# LIN-INTERFACES.net
KiCad netlist of a schematic drawn in Altium Designer
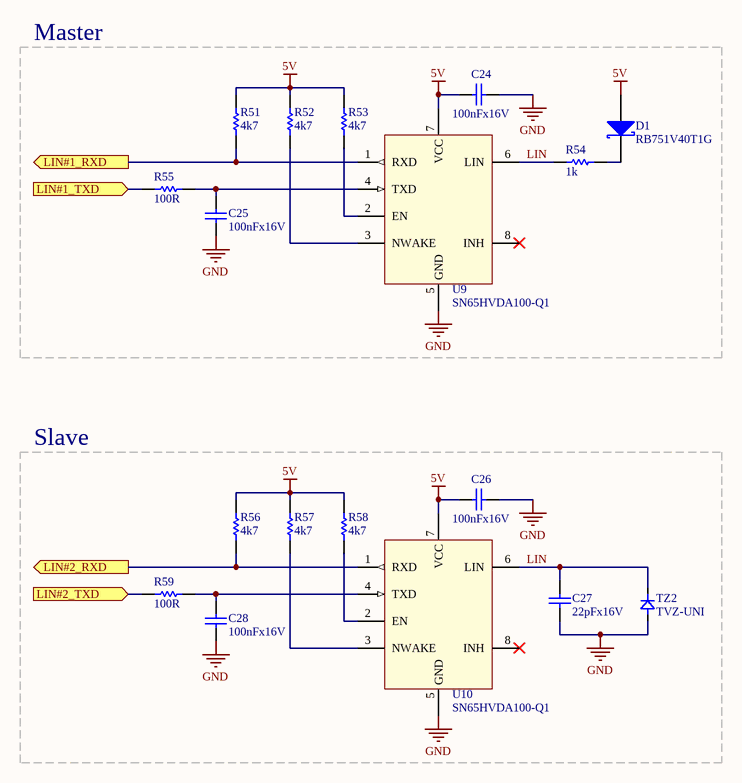
[diagram p0: LIN-INTERFACES.SchDoc]

(export (version "E")
  (design (tool "Eeschema 10.0.6"))
  (components
    (comp (ref "C24")
      (value "100nFx16V")
      (footprint "DISC-0603")
      (description "Capacitor")
      (libsource (lib "IntLib") (part "Cap"))
    )
    (comp (ref "C25")
      (value "100nFx16V")
      (footprint "DISC-0603")
      (description "Capacitor")
      (libsource (lib "IntLib") (part "Cap"))
    )
    (comp (ref "C26")
      (value "100nFx16V")
      (footprint "DISC-0603")
      (description "Capacitor")
      (libsource (lib "IntLib") (part "Cap"))
    )
    (comp (ref "C27") (value "22pFx16V") (footprint "DISC-0603") (libsource (lib "IntLib") (part "Cap")))
    (comp (ref "C28")
      (value "100nFx16V")
      (footprint "DISC-0603")
      (description "Capacitor")
      (libsource (lib "IntLib") (part "Cap"))
    )
    (comp (ref "D1")
      (value "RB751V40T1G")
      (footprint "DISC-SOD-323")
      (description "Schottky Diode")
      (fields (field (name "PUBLISHER") "Altium Limited"))
      (libsource (lib "IntLib") (part "D Schottky"))
    )
    (comp (ref "R51")
      (value "4k7")
      (footprint "DISC-0603")
      (description "Resistor")
      (libsource (lib "IntLib") (part "Res"))
    )
    (comp (ref "R52")
      (value "4k7")
      (footprint "DISC-0603")
      (description "Resistor")
      (libsource (lib "IntLib") (part "Res"))
    )
    (comp (ref "R53")
      (value "4k7")
      (footprint "DISC-0603")
      (description "Resistor")
      (libsource (lib "IntLib") (part "Res"))
    )
    (comp (ref "R54")
      (value "1k")
      (footprint "DISC-0603")
      (description "Resistor")
      (libsource (lib "IntLib") (part "Res"))
    )
    (comp (ref "R55")
      (value "100R")
      (footprint "DISC-0603")
      (description "Resistor")
      (libsource (lib "IntLib") (part "Res"))
    )
    (comp (ref "R56")
      (value "4k7")
      (footprint "DISC-0603")
      (description "Resistor")
      (libsource (lib "IntLib") (part "Res"))
    )
    (comp (ref "R57")
      (value "4k7")
      (footprint "DISC-0603")
      (description "Resistor")
      (libsource (lib "IntLib") (part "Res"))
    )
    (comp (ref "R58")
      (value "4k7")
      (footprint "DISC-0603")
      (description "Resistor")
      (libsource (lib "IntLib") (part "Res"))
    )
    (comp (ref "R59")
      (value "100R")
      (footprint "DISC-0603")
      (description "Resistor")
      (libsource (lib "IntLib") (part "Res"))
    )
    (comp (ref "TZ2")
      (value "TVZ-UNI")
      (footprint "DISC-SOD-323")
      (description "TVZ-Unidirectional")
      (libsource (lib "IntLib") (part "TVZ-Unidirectional"))
    )
    (comp (ref "U9")
      (value "SN65HVDA100-Q1")
      (footprint "CI-SOIC-8")
      (description "LIN Transceiver")
      (libsource (lib "IntLib") (part "SN65HVDA100-Q1"))
    )
    (comp (ref "U10")
      (value "SN65HVDA100-Q1")
      (footprint "CI-SOIC-8")
      (description "LIN Transceiver")
      (libsource (lib "IntLib") (part "SN65HVDA100-Q1"))
    )
  )
  (nets
    (net (code "1") (name "/LIN") (class "Default")
      (node (ref "C27") (pin "2") (pinfunction "2_2") (pintype "passive"))
      (node (ref "R54") (pin "2") (pinfunction "2_2") (pintype "passive"))
      (node (ref "TZ2") (pin "2") (pinfunction "C_2") (pintype "passive"))
      (node (ref "U10") (pin "6") (pinfunction "LIN_6") (pintype "passive"))
      (node (ref "U9") (pin "6") (pinfunction "LIN_6") (pintype "passive"))
    )
    (net (code "2") (name "/LIN#1_RXD") (class "Default")
      (node (ref "R51") (pin "1") (pinfunction "1_1") (pintype "passive"))
      (node (ref "U9") (pin "1") (pinfunction "RXD_1") (pintype "output"))
    )
    (net (code "3") (name "/LIN#1_TXD") (class "Default")
      (node (ref "R55") (pin "2") (pinfunction "2_2") (pintype "passive"))
    )
    (net (code "4") (name "/LIN#2_RXD") (class "Default")
      (node (ref "R56") (pin "1") (pinfunction "1_1") (pintype "passive"))
      (node (ref "U10") (pin "1") (pinfunction "RXD_1") (pintype "output"))
    )
    (net (code "5") (name "/LIN#2_TXD") (class "Default")
      (node (ref "R59") (pin "2") (pinfunction "2_2") (pintype "passive"))
    )
    (net (code "6") (name "5V") (class "Default")
      (node (ref "C24") (pin "2") (pinfunction "2_2") (pintype "passive"))
      (node (ref "C26") (pin "2") (pinfunction "2_2") (pintype "passive"))
      (node (ref "D1") (pin "1") (pinfunction "A_1") (pintype "passive"))
      (node (ref "R51") (pin "2") (pinfunction "2_2") (pintype "passive"))
      (node (ref "R52") (pin "2") (pinfunction "2_2") (pintype "passive"))
      (node (ref "R53") (pin "2") (pinfunction "2_2") (pintype "passive"))
      (node (ref "R56") (pin "2") (pinfunction "2_2") (pintype "passive"))
      (node (ref "R57") (pin "2") (pinfunction "2_2") (pintype "passive"))
      (node (ref "R58") (pin "2") (pinfunction "2_2") (pintype "passive"))
      (node (ref "U10") (pin "7") (pinfunction "VCC_7") (pintype "power_in"))
      (node (ref "U9") (pin "7") (pinfunction "VCC_7") (pintype "power_in"))
    )
    (net (code "7") (name "GND") (class "Default")
      (node (ref "C24") (pin "1") (pinfunction "1_1") (pintype "passive"))
      (node (ref "C25") (pin "1") (pinfunction "1_1") (pintype "passive"))
      (node (ref "C26") (pin "1") (pinfunction "1_1") (pintype "passive"))
      (node (ref "C27") (pin "1") (pinfunction "1_1") (pintype "passive"))
      (node (ref "C28") (pin "1") (pinfunction "1_1") (pintype "passive"))
      (node (ref "TZ2") (pin "1") (pinfunction "A_1") (pintype "passive"))
      (node (ref "U10") (pin "5") (pinfunction "GND_5") (pintype "power_in"))
      (node (ref "U9") (pin "5") (pinfunction "GND_5") (pintype "power_in"))
    )
    (net (code "8") (name "Net-(D1-K)") (class "Default")
      (node (ref "D1") (pin "2") (pinfunction "K_2") (pintype "passive"))
      (node (ref "R54") (pin "1") (pinfunction "1_1") (pintype "passive"))
    )
    (net (code "9") (name "Net-(U9-EN)") (class "Default")
      (node (ref "R53") (pin "1") (pinfunction "1_1") (pintype "passive"))
      (node (ref "U9") (pin "2") (pinfunction "EN_2") (pintype "passive"))
    )
    (net (code "10") (name "Net-(U9-NWAKE)") (class "Default")
      (node (ref "R52") (pin "1") (pinfunction "1_1") (pintype "passive"))
      (node (ref "U9") (pin "3") (pinfunction "NWAKE_3") (pintype "passive"))
    )
    (net (code "11") (name "Net-(U9-TXD)") (class "Default")
      (node (ref "C25") (pin "2") (pinfunction "2_2") (pintype "passive"))
      (node (ref "R55") (pin "1") (pinfunction "1_1") (pintype "passive"))
      (node (ref "U9") (pin "4") (pinfunction "TXD_4") (pintype "input"))
    )
    (net (code "12") (name "Net-(U10-EN)") (class "Default")
      (node (ref "R58") (pin "1") (pinfunction "1_1") (pintype "passive"))
      (node (ref "U10") (pin "2") (pinfunction "EN_2") (pintype "passive"))
    )
    (net (code "13") (name "Net-(U10-NWAKE)") (class "Default")
      (node (ref "R57") (pin "1") (pinfunction "1_1") (pintype "passive"))
      (node (ref "U10") (pin "3") (pinfunction "NWAKE_3") (pintype "passive"))
    )
    (net (code "14") (name "Net-(U10-TXD)") (class "Default")
      (node (ref "C28") (pin "2") (pinfunction "2_2") (pintype "passive"))
      (node (ref "R59") (pin "1") (pinfunction "1_1") (pintype "passive"))
      (node (ref "U10") (pin "4") (pinfunction "TXD_4") (pintype "input"))
    )
    (net (code "15") (name "unconnected-(U9-INH-Pad8)") (class "Default")
      (node (ref "U9") (pin "8") (pinfunction "INH_8") (pintype "passive+no_connect"))
    )
    (net (code "16") (name "unconnected-(U10-INH-Pad8)") (class "Default")
      (node (ref "U10") (pin "8") (pinfunction "INH_8") (pintype "passive+no_connect"))
    )
  )
)
